# SparkFun_Qwiic_UV_Sensor_AS7331.net
KiCad netlist of a schematic drawn in EAGLE
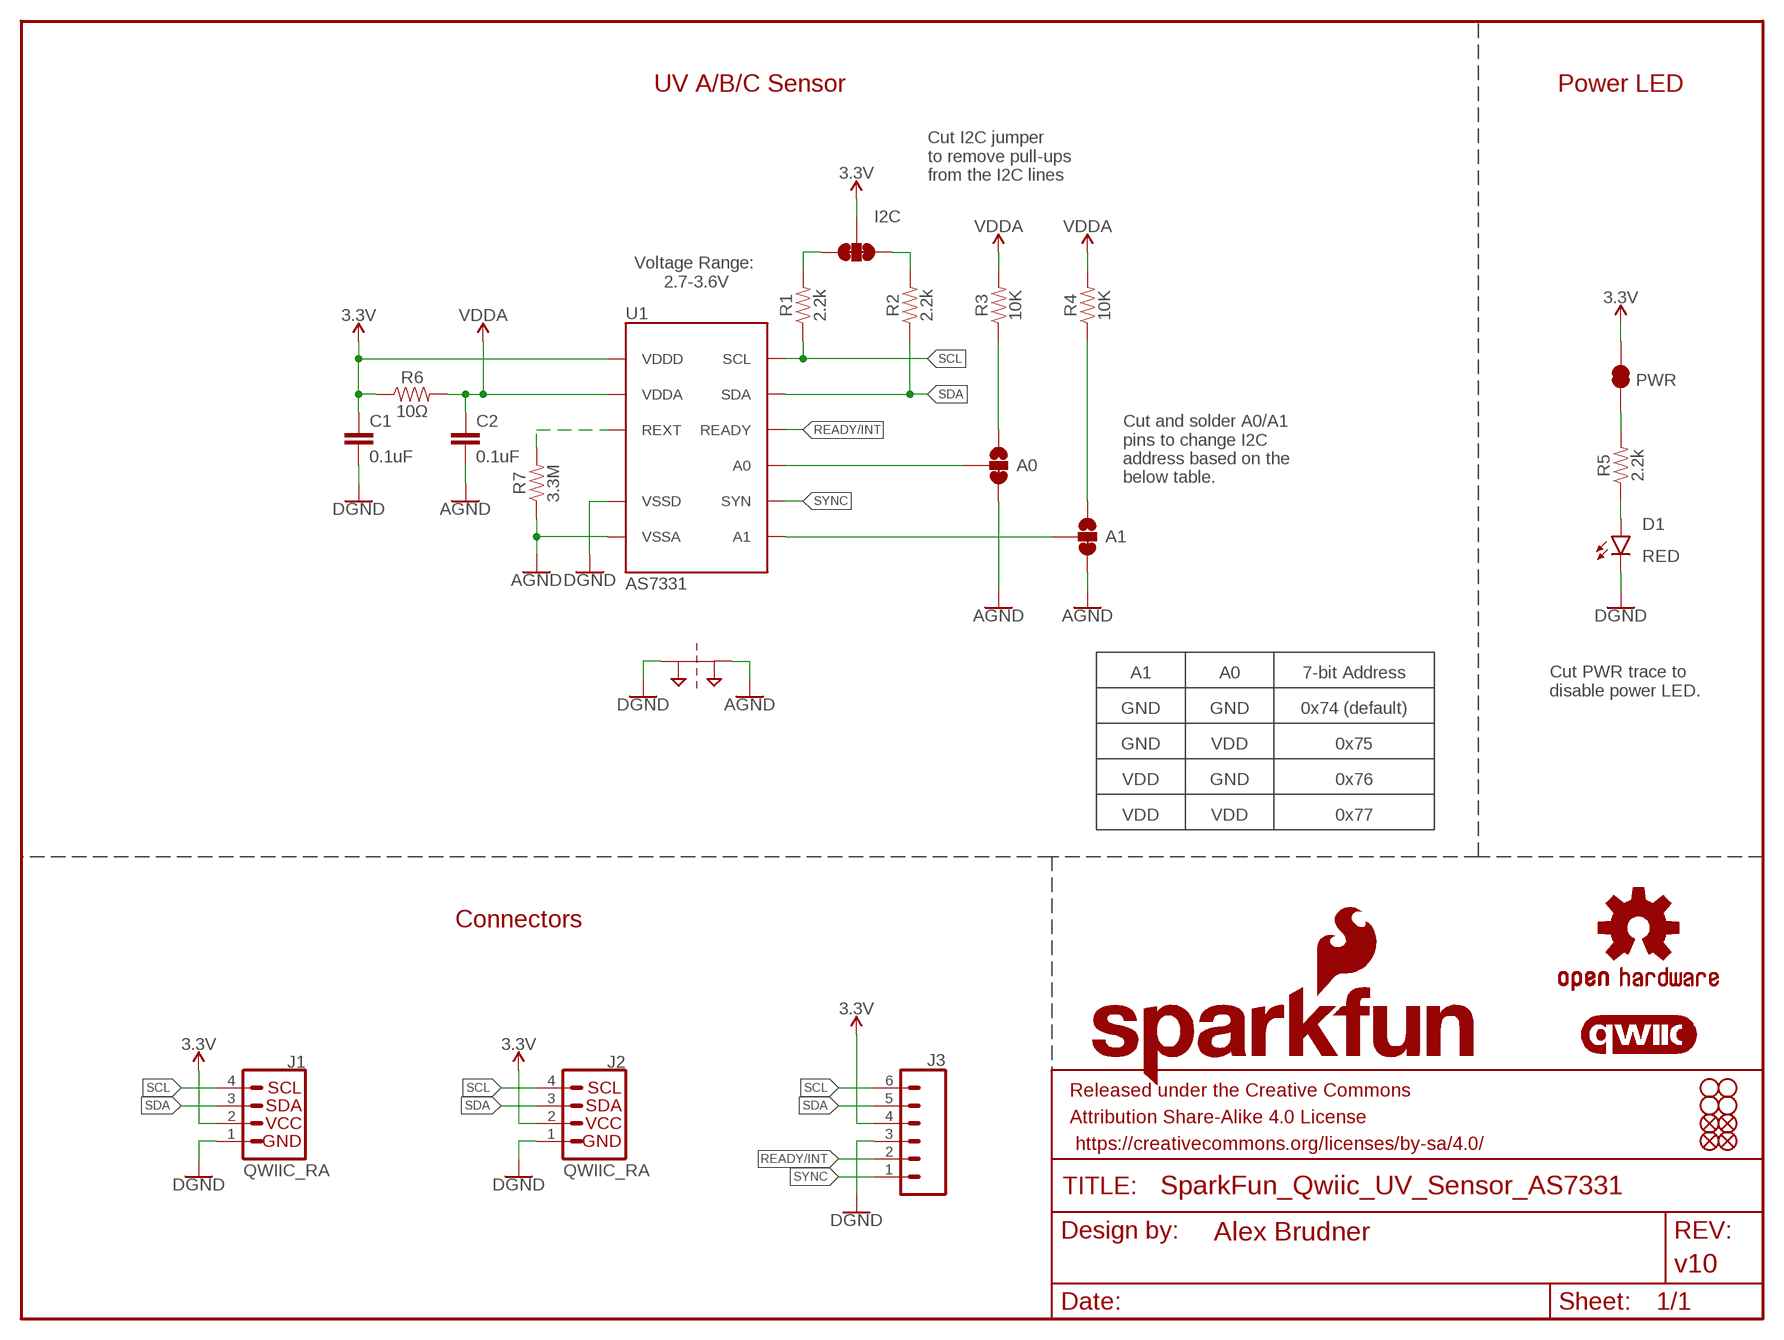
[diagram p0: schematic, sheet 1]

(export (version "E")
  (design (tool "Eeschema 10.0.6"))
  (components
    (comp (ref "A0")
      (value "JUMPER-SMT_3_1-NC_TRACE_SILK")
      (footprint "eagle-import:SMT-JUMPER_3_1-NC_TRACE_SILK")
      (libsource (lib "eagle-import") (part "JUMPER-SMT_3_1-NC_TRACE_SILK"))
    )
    (comp (ref "A1")
      (value "JUMPER-SMT_3_1-NC_TRACE_SILK")
      (footprint "eagle-import:SMT-JUMPER_3_1-NC_TRACE_SILK")
      (libsource (lib "eagle-import") (part "JUMPER-SMT_3_1-NC_TRACE_SILK"))
    )
    (comp (ref "C1")
      (value "0.1uF")
      (footprint "eagle-import:0402-TIGHT")
      (libsource (lib "eagle-import") (part "0.1UF-0402T-6.3V-10%-X7R"))
    )
    (comp (ref "C2")
      (value "0.1uF")
      (footprint "eagle-import:0402-TIGHT")
      (libsource (lib "eagle-import") (part "0.1UF-0402T-6.3V-10%-X7R"))
    )
    (comp (ref "D1")
      (value "RED")
      (footprint "eagle-import:LED-0402")
      (libsource (lib "eagle-import") (part "LED-RED_0402"))
    )
    (comp (ref "FD1")
      (value "FIDUCIALUFIDUCIAL")
      (footprint "eagle-import:FIDUCIAL-MICRO")
      (libsource (lib "eagle-import") (part "FIDUCIALUFIDUCIAL"))
    )
    (comp (ref "FD2")
      (value "FIDUCIALUFIDUCIAL")
      (footprint "eagle-import:FIDUCIAL-MICRO")
      (libsource (lib "eagle-import") (part "FIDUCIALUFIDUCIAL"))
    )
    (comp (ref "FD3")
      (value "FIDUCIALUFIDUCIAL")
      (footprint "eagle-import:FIDUCIAL-MICRO")
      (libsource (lib "eagle-import") (part "FIDUCIALUFIDUCIAL"))
    )
    (comp (ref "FD4")
      (value "FIDUCIALUFIDUCIAL")
      (footprint "eagle-import:FIDUCIAL-MICRO")
      (libsource (lib "eagle-import") (part "FIDUCIALUFIDUCIAL"))
    )
    (comp (ref "FRAME1")
      (value "FRAME-LETTER")
      (footprint "eagle-import:CREATIVE_COMMONS")
      (fields (field (name "DESIGNER") "Alex Brudner") (field (name "REV") "v10"))
      (libsource (lib "eagle-import") (part "FRAME-LETTER"))
    )
    (comp (ref "H1")
      (value "STAND-OFFTIGHT")
      (footprint "eagle-import:STAND-OFF-TIGHT")
      (libsource (lib "eagle-import") (part "STAND-OFFTIGHT"))
    )
    (comp (ref "H2")
      (value "STAND-OFFTIGHT")
      (footprint "eagle-import:STAND-OFF-TIGHT")
      (libsource (lib "eagle-import") (part "STAND-OFFTIGHT"))
    )
    (comp (ref "H3")
      (value "STAND-OFFTIGHT")
      (footprint "eagle-import:STAND-OFF-TIGHT")
      (libsource (lib "eagle-import") (part "STAND-OFFTIGHT"))
    )
    (comp (ref "H4")
      (value "STAND-OFFTIGHT")
      (footprint "eagle-import:STAND-OFF-TIGHT")
      (libsource (lib "eagle-import") (part "STAND-OFFTIGHT"))
    )
    (comp (ref "I2C")
      (value "JUMPER-SMT_3_2-NC_TRACE_SILK")
      (footprint "eagle-import:SMT-JUMPER_3_2-NC_TRACE_SILK")
      (libsource (lib "eagle-import") (part "JUMPER-SMT_3_2-NC_TRACE_SILK"))
    )
    (comp (ref "J1")
      (value "QWIIC_RA")
      (footprint "eagle-import:JST04_1MM_RA")
      (libsource (lib "eagle-import") (part "QWIIC_CONNECTORJS-1MM"))
    )
    (comp (ref "J2")
      (value "QWIIC_RA")
      (footprint "eagle-import:JST04_1MM_RA")
      (libsource (lib "eagle-import") (part "QWIIC_CONNECTORJS-1MM"))
    )
    (comp (ref "J3")
      (value "CONN_06NO_SILK_NO_POP")
      (footprint "eagle-import:1X06_NO_SILK")
      (libsource (lib "eagle-import") (part "CONN_06NO_SILK_NO_POP"))
    )
    (comp (ref "LOGO1")
      (value "SFE_LOGO_NAME_FLAME.1_INCH")
      (footprint "eagle-import:SFE_LOGO_NAME_FLAME_.1")
      (libsource (lib "eagle-import") (part "SFE_LOGO_NAME_FLAME.1_INCH"))
    )
    (comp (ref "LOGO2")
      (value "QWIIC_LOGO_CONNECTOR")
      (footprint "eagle-import:QWIIC_5.5MM")
      (libsource (lib "eagle-import") (part "QWIIC_LOGO_CONNECTOR"))
    )
    (comp (ref "LOGO3")
      (value "OSHW-LOGOMINI")
      (footprint "eagle-import:OSHW-LOGO-MINI")
      (libsource (lib "eagle-import") (part "OSHW-LOGOMINI"))
    )
    (comp (ref "PWR")
      (value "JUMPER-SMT_2_NC_TRACE_SILK")
      (footprint "eagle-import:SMT-JUMPER_2_NC_TRACE_SILK")
      (libsource (lib "eagle-import") (part "JUMPER-SMT_2_NC_TRACE_SILK"))
    )
    (comp (ref "R1")
      (value "2.2k")
      (footprint "eagle-import:0402-TIGHT")
      (libsource (lib "eagle-import") (part "2.2KOHM-0402T-1/16W-1%"))
    )
    (comp (ref "R2")
      (value "2.2k")
      (footprint "eagle-import:0402-TIGHT")
      (libsource (lib "eagle-import") (part "2.2KOHM-0402T-1/16W-1%"))
    )
    (comp (ref "R3")
      (value "10K")
      (footprint "eagle-import:0402-TIGHT")
      (libsource (lib "eagle-import") (part "10KOHM-0402-1/10W-0.1%"))
    )
    (comp (ref "R4")
      (value "10K")
      (footprint "eagle-import:0402-TIGHT")
      (libsource (lib "eagle-import") (part "10KOHM-0402-1/10W-0.1%"))
    )
    (comp (ref "R5")
      (value "2.2k")
      (footprint "eagle-import:0402-TIGHT")
      (libsource (lib "eagle-import") (part "2.2KOHM-0402T-1/16W-1%"))
    )
    (comp (ref "R6")
      (value "10Ω")
      (footprint "eagle-import:0402-TIGHT")
      (libsource (lib "eagle-import") (part "10OHM-0402-1/16W-5%"))
    )
    (comp (ref "R7")
      (value "3.3M")
      (footprint "eagle-import:1206")
      (libsource (lib "eagle-import") (part "3.3MOHM"))
    )
    (comp (ref "SUPPLYTIE1")
      (value "2PT_GND_TIE")
      (footprint "eagle-import:2PT_GND_TIE")
      (libsource (lib "eagle-import") (part "2PT_GND_TIE"))
    )
    (comp (ref "U1")
      (value "AS7331")
      (footprint "eagle-import:OLGA16")
      (libsource (lib "eagle-import") (part "UV_SENSOR_AS7331"))
    )
  )
  (nets
    (net (code "1") (name "3.3V") (class "Default")
      (node (ref "C1") (pin "1") (pinfunction "1_1") (pintype "passive"))
      (node (ref "I2C") (pin "2") (pinfunction "2_2") (pintype "passive"))
      (node (ref "J1") (pin "2") (pinfunction "2_2") (pintype "power_in"))
      (node (ref "J2") (pin "2") (pinfunction "2_2") (pintype "power_in"))
      (node (ref "J3") (pin "4") (pinfunction "4_4") (pintype "passive"))
      (node (ref "PWR") (pin "2") (pinfunction "2_2") (pintype "passive"))
      (node (ref "R6") (pin "1") (pinfunction "1_1") (pintype "passive"))
      (node (ref "U1") (pin "10") (pinfunction "VDDD_10") (pintype "power_in"))
    )
    (net (code "2") (name "AGND") (class "Default")
      (node (ref "A0") (pin "3") (pinfunction "3_3") (pintype "passive"))
      (node (ref "A1") (pin "3") (pinfunction "3_3") (pintype "passive"))
      (node (ref "C2") (pin "2") (pinfunction "2_2") (pintype "passive"))
      (node (ref "R7") (pin "1") (pinfunction "1_1") (pintype "passive"))
      (node (ref "SUPPLYTIE1") (pin "P$2") (pinfunction "P$2_P$2") (pintype "bidirectional"))
      (node (ref "U1") (pin "1") (pinfunction "VSSA_1") (pintype "power_in"))
      (node (ref "U1") (pin "15") (pinfunction "VSSA_15") (pintype "power_in"))
      (node (ref "U1") (pin "16") (pinfunction "VSSA_16") (pintype "power_in"))
      (node (ref "U1") (pin "2") (pinfunction "VSSA_2") (pintype "power_in"))
      (node (ref "U1") (pin "5") (pinfunction "VSSA_5") (pintype "power_in"))
      (node (ref "U1") (pin "6") (pinfunction "VSSA_6") (pintype "power_in"))
    )
    (net (code "3") (name "DGND") (class "Default")
      (node (ref "C1") (pin "2") (pinfunction "2_2") (pintype "passive"))
      (node (ref "D1") (pin "C") (pinfunction "C_C") (pintype "passive"))
      (node (ref "J1") (pin "1") (pinfunction "1_1") (pintype "power_in"))
      (node (ref "J2") (pin "1") (pinfunction "1_1") (pintype "power_in"))
      (node (ref "J3") (pin "3") (pinfunction "3_3") (pintype "passive"))
      (node (ref "SUPPLYTIE1") (pin "P$1") (pinfunction "P$1_P$1") (pintype "bidirectional"))
      (node (ref "U1") (pin "11") (pinfunction "VSSD_11") (pintype "power_in"))
    )
    (net (code "4") (name "Net-(A0-Pad1)") (class "Default")
      (node (ref "A0") (pin "1") (pinfunction "1_1") (pintype "passive"))
      (node (ref "R3") (pin "1") (pinfunction "1_1") (pintype "passive"))
    )
    (net (code "5") (name "Net-(A1-Pad1)") (class "Default")
      (node (ref "A1") (pin "1") (pinfunction "1_1") (pintype "passive"))
      (node (ref "R4") (pin "1") (pinfunction "1_1") (pintype "passive"))
    )
    (net (code "6") (name "Net-(D1-PadA)") (class "Default")
      (node (ref "D1") (pin "A") (pinfunction "A_A") (pintype "passive"))
      (node (ref "R5") (pin "1") (pinfunction "1_1") (pintype "passive"))
    )
    (net (code "7") (name "Net-(I2C-Pad1)") (class "Default")
      (node (ref "I2C") (pin "1") (pinfunction "1_1") (pintype "passive"))
      (node (ref "R2") (pin "2") (pinfunction "2_2") (pintype "passive"))
    )
    (net (code "8") (name "Net-(I2C-Pad3)") (class "Default")
      (node (ref "I2C") (pin "3") (pinfunction "3_3") (pintype "passive"))
      (node (ref "R1") (pin "2") (pinfunction "2_2") (pintype "passive"))
    )
    (net (code "9") (name "Net-(PWR-Pad1)") (class "Default")
      (node (ref "PWR") (pin "1") (pinfunction "1_1") (pintype "passive"))
      (node (ref "R5") (pin "2") (pinfunction "2_2") (pintype "passive"))
    )
    (net (code "10") (name "Net-(U1-A0)") (class "Default")
      (node (ref "A0") (pin "2") (pinfunction "2_2") (pintype "passive"))
      (node (ref "U1") (pin "14") (pinfunction "A0_14") (pintype "input"))
    )
    (net (code "11") (name "Net-(U1-A1)") (class "Default")
      (node (ref "A1") (pin "2") (pinfunction "2_2") (pintype "passive"))
      (node (ref "U1") (pin "7") (pinfunction "A1_7") (pintype "input"))
    )
    (net (code "12") (name "Net-(U1-REXT)") (class "Default")
      (node (ref "R7") (pin "2") (pinfunction "2_2") (pintype "passive"))
      (node (ref "U1") (pin "4") (pinfunction "REXT_4") (pintype "bidirectional"))
    )
    (net (code "13") (name "READY{slash}INT") (class "Default")
      (node (ref "J3") (pin "2") (pinfunction "2_2") (pintype "passive"))
      (node (ref "U1") (pin "9") (pinfunction "READY_9") (pintype "output"))
    )
    (net (code "14") (name "SCL") (class "Default")
      (node (ref "J1") (pin "4") (pinfunction "4_4") (pintype "passive"))
      (node (ref "J2") (pin "4") (pinfunction "4_4") (pintype "passive"))
      (node (ref "J3") (pin "6") (pinfunction "6_6") (pintype "passive"))
      (node (ref "R1") (pin "1") (pinfunction "1_1") (pintype "passive"))
      (node (ref "U1") (pin "13") (pinfunction "SCL_13") (pintype "input"))
    )
    (net (code "15") (name "SDA") (class "Default")
      (node (ref "J1") (pin "3") (pinfunction "3_3") (pintype "passive"))
      (node (ref "J2") (pin "3") (pinfunction "3_3") (pintype "passive"))
      (node (ref "J3") (pin "5") (pinfunction "5_5") (pintype "passive"))
      (node (ref "R2") (pin "1") (pinfunction "1_1") (pintype "passive"))
      (node (ref "U1") (pin "12") (pinfunction "SDA_12") (pintype "bidirectional"))
    )
    (net (code "16") (name "SYNC") (class "Default")
      (node (ref "J3") (pin "1") (pinfunction "1_1") (pintype "passive"))
      (node (ref "U1") (pin "8") (pinfunction "SYN_8") (pintype "input"))
    )
    (net (code "17") (name "VDDA") (class "Default")
      (node (ref "C2") (pin "1") (pinfunction "1_1") (pintype "passive"))
      (node (ref "R3") (pin "2") (pinfunction "2_2") (pintype "passive"))
      (node (ref "R4") (pin "2") (pinfunction "2_2") (pintype "passive"))
      (node (ref "R6") (pin "2") (pinfunction "2_2") (pintype "passive"))
      (node (ref "U1") (pin "3") (pinfunction "VDDA_3") (pintype "power_in"))
    )
  )
)
